# module-si7021-mpl3115.net
KiCad netlist of a schematic drawn in EAGLE
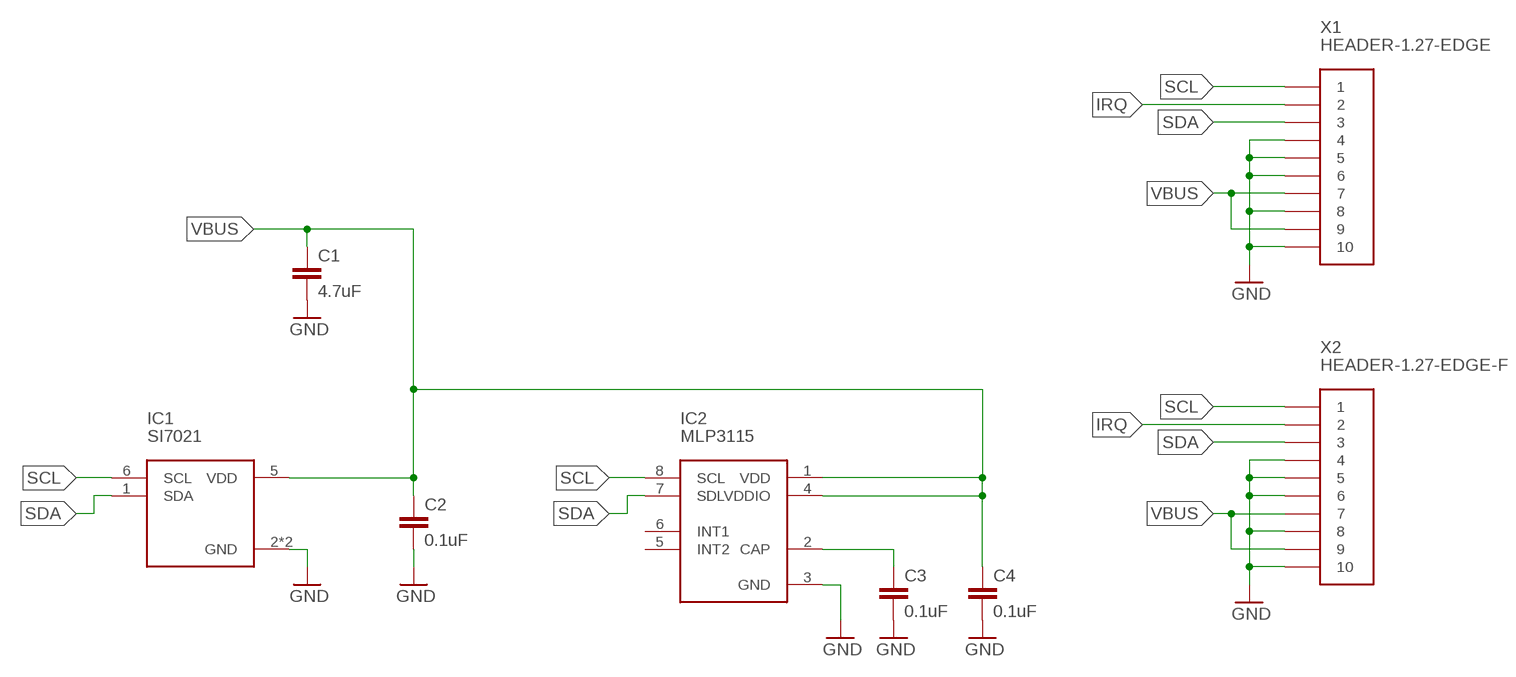
[diagram p0: schematic, sheet 1]

(export (version "E")
  (design (tool "Eeschema 10.0.6"))
  (components
    (comp (ref "C1")
      (value "4.7uF")
      (footprint "eagle-import:C0805")
      (libsource (lib "eagle-import") (part "C-EUC0805"))
    )
    (comp (ref "C2")
      (value "0.1uF")
      (footprint "eagle-import:C0603")
      (libsource (lib "eagle-import") (part "C-EUC0603"))
    )
    (comp (ref "C3")
      (value "0.1uF")
      (footprint "eagle-import:C0603")
      (libsource (lib "eagle-import") (part "C-EUC0603"))
    )
    (comp (ref "C4")
      (value "0.1uF")
      (footprint "eagle-import:C0603")
      (libsource (lib "eagle-import") (part "C-EUC0603"))
    )
    (comp (ref "IC1")
      (value "SI7021")
      (footprint "eagle-import:DFN6-3X3")
      (libsource (lib "eagle-import") (part "SI7021"))
    )
    (comp (ref "IC2")
      (value "MLP3115")
      (footprint "eagle-import:LGA8-3X3X1.25")
      (libsource (lib "eagle-import") (part "MLP3115"))
    )
    (comp (ref "X1")
      (value "HEADER-1.27-EDGE")
      (footprint "eagle-import:HEADER-1.27-EDGE")
      (libsource (lib "eagle-import") (part "HEADER-1.27-EDGE"))
    )
    (comp (ref "X2")
      (value "HEADER-1.27-EDGE-F")
      (footprint "eagle-import:HEADER-1.27-EDGE-F")
      (libsource (lib "eagle-import") (part "HEADER-1.27-EDGE-F"))
    )
  )
  (nets
    (net (code "1") (name "GND") (class "Default")
      (node (ref "C1") (pin "2") (pinfunction "2_2") (pintype "passive"))
      (node (ref "C2") (pin "2") (pinfunction "2_2") (pintype "passive"))
      (node (ref "C3") (pin "2") (pinfunction "2_2") (pintype "passive"))
      (node (ref "C4") (pin "2") (pinfunction "2_2") (pintype "passive"))
      (node (ref "IC1") (pin "2") (pinfunction "GND_2") (pintype "bidirectional"))
      (node (ref "IC1") (pin "PAD") (pinfunction "GND_PAD") (pintype "bidirectional"))
      (node (ref "IC2") (pin "3") (pinfunction "GND_3") (pintype "bidirectional"))
      (node (ref "X1") (pin "10") (pinfunction "10_10") (pintype "bidirectional"))
      (node (ref "X1") (pin "4") (pinfunction "4_4") (pintype "bidirectional"))
      (node (ref "X1") (pin "5") (pinfunction "5_5") (pintype "bidirectional"))
      (node (ref "X1") (pin "6") (pinfunction "6_6") (pintype "bidirectional"))
      (node (ref "X1") (pin "8") (pinfunction "8_8") (pintype "bidirectional"))
      (node (ref "X2") (pin "10") (pinfunction "10_10") (pintype "bidirectional"))
      (node (ref "X2") (pin "4") (pinfunction "4_4") (pintype "bidirectional"))
      (node (ref "X2") (pin "5") (pinfunction "5_5") (pintype "bidirectional"))
      (node (ref "X2") (pin "6") (pinfunction "6_6") (pintype "bidirectional"))
      (node (ref "X2") (pin "8") (pinfunction "8_8") (pintype "bidirectional"))
    )
    (net (code "2") (name "IRQ") (class "Default")
      (node (ref "X1") (pin "2") (pinfunction "2_2") (pintype "bidirectional"))
      (node (ref "X2") (pin "2") (pinfunction "2_2") (pintype "bidirectional"))
    )
    (net (code "3") (name "Net-(IC2-CAP)") (class "Default")
      (node (ref "C3") (pin "1") (pinfunction "1_1") (pintype "passive"))
      (node (ref "IC2") (pin "2") (pinfunction "CAP_2") (pintype "bidirectional"))
    )
    (net (code "4") (name "SCL") (class "Default")
      (node (ref "IC1") (pin "6") (pinfunction "SCL_6") (pintype "bidirectional"))
      (node (ref "IC2") (pin "8") (pinfunction "SCL_8") (pintype "bidirectional"))
      (node (ref "X1") (pin "1") (pinfunction "1_1") (pintype "bidirectional"))
      (node (ref "X2") (pin "1") (pinfunction "1_1") (pintype "bidirectional"))
    )
    (net (code "5") (name "SDA") (class "Default")
      (node (ref "IC1") (pin "1") (pinfunction "SDA_1") (pintype "bidirectional"))
      (node (ref "IC2") (pin "7") (pinfunction "SDL_7") (pintype "bidirectional"))
      (node (ref "X1") (pin "3") (pinfunction "3_3") (pintype "bidirectional"))
      (node (ref "X2") (pin "3") (pinfunction "3_3") (pintype "bidirectional"))
    )
    (net (code "6") (name "VBUS") (class "Default")
      (node (ref "C1") (pin "1") (pinfunction "1_1") (pintype "passive"))
      (node (ref "C2") (pin "1") (pinfunction "1_1") (pintype "passive"))
      (node (ref "C4") (pin "1") (pinfunction "1_1") (pintype "passive"))
      (node (ref "IC1") (pin "5") (pinfunction "VDD_5") (pintype "bidirectional"))
      (node (ref "IC2") (pin "1") (pinfunction "VDD_1") (pintype "bidirectional"))
      (node (ref "IC2") (pin "4") (pinfunction "VDDIO_4") (pintype "bidirectional"))
      (node (ref "X1") (pin "7") (pinfunction "7_7") (pintype "bidirectional"))
      (node (ref "X1") (pin "9") (pinfunction "9_9") (pintype "bidirectional"))
      (node (ref "X2") (pin "7") (pinfunction "7_7") (pintype "bidirectional"))
      (node (ref "X2") (pin "9") (pinfunction "9_9") (pintype "bidirectional"))
    )
    (net (code "7") (name "unconnected-(IC2-INT1-Pad6)") (class "Default")
      (node (ref "IC2") (pin "6") (pinfunction "INT1_6") (pintype "bidirectional"))
    )
    (net (code "8") (name "unconnected-(IC2-INT2-Pad5)") (class "Default")
      (node (ref "IC2") (pin "5") (pinfunction "INT2_5") (pintype "bidirectional"))
    )
  )
)
